# clock.net
KiCad netlist of a schematic drawn in EAGLE
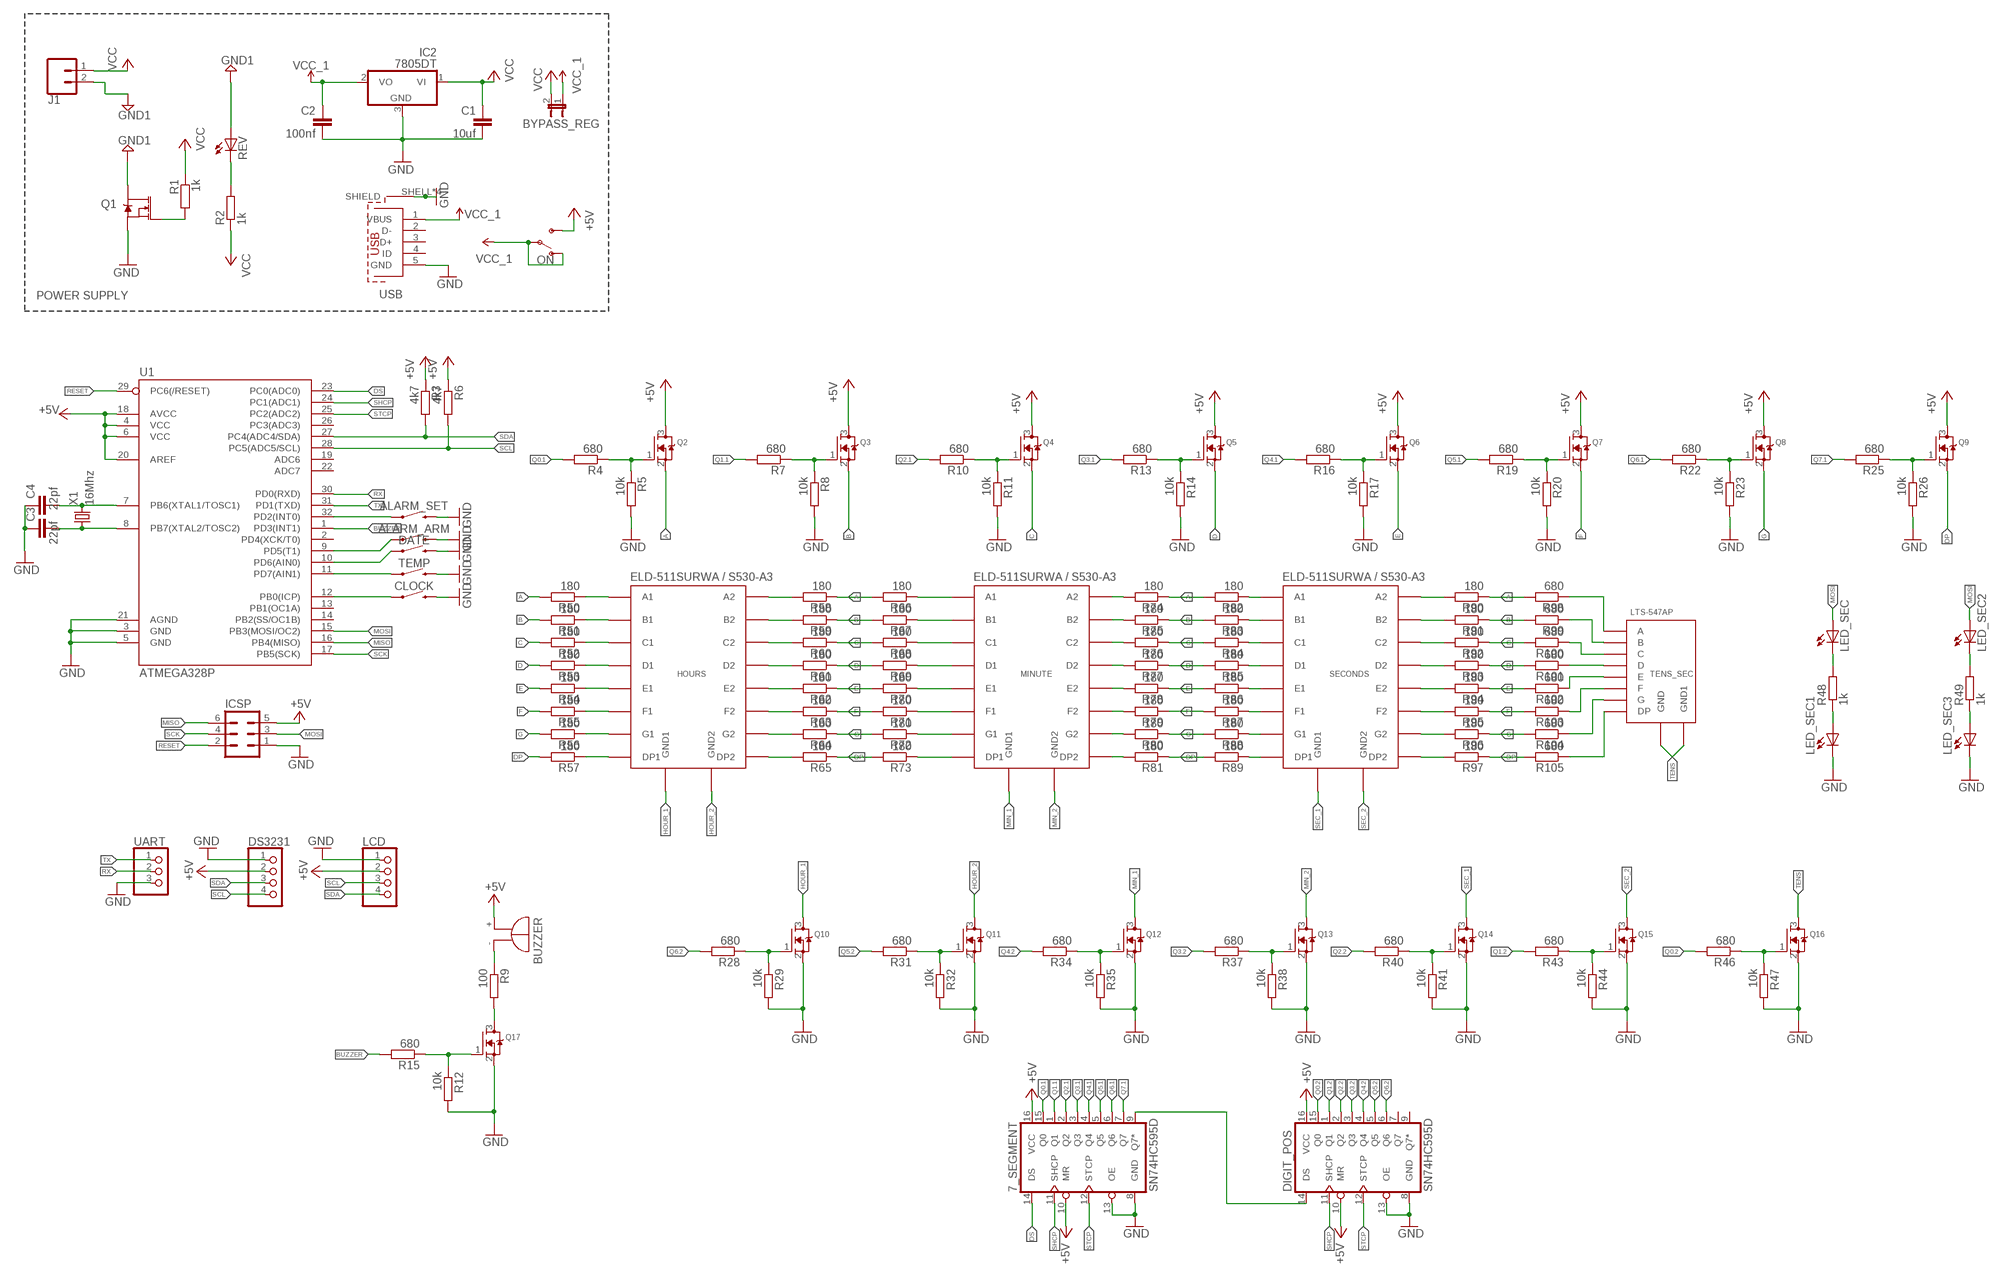
[diagram p0: schematic, sheet 1]

(export (version "E")
  (design (tool "Eeschema 10.0.6"))
  (components
    (comp (ref "7_SEGMENT")
      (value "SN74HC595D")
      (footprint "eagle-import:SO16")
      (libsource (lib "eagle-import") (part "74595DHC"))
    )
    (comp (ref "ALARM_ARM")
      (value "MOMENTARY-SWITCH-SPST-SMD-5.2MM")
      (footprint "eagle-import:TACTILE_SWITCH_SMD_5.2MM")
      (libsource (lib "eagle-import") (part "MOMENTARY-SWITCH-SPST-SMD-5.2MM"))
    )
    (comp (ref "ALARM_SET")
      (value "MOMENTARY-SWITCH-SPST-SMD-5.2MM")
      (footprint "eagle-import:TACTILE_SWITCH_SMD_5.2MM")
      (libsource (lib "eagle-import") (part "MOMENTARY-SWITCH-SPST-SMD-5.2MM"))
    )
    (comp (ref "BUZZER")
      (value "EB2209A")
      (footprint "eagle-import:EB2209A")
      (libsource (lib "eagle-import") (part "EB2209A"))
    )
    (comp (ref "BYPASS_REG")
      (value "JUMPER-2PTH")
      (footprint "eagle-import:1X02")
      (libsource (lib "eagle-import") (part "JUMPER-2PTH"))
    )
    (comp (ref "C1")
      (value "10uf")
      (footprint "eagle-import:C1206")
      (libsource (lib "eagle-import") (part "C-EUC1206"))
    )
    (comp (ref "C2")
      (value "100nf")
      (footprint "eagle-import:C1206")
      (libsource (lib "eagle-import") (part "C-EUC1206"))
    )
    (comp (ref "C3")
      (value "22pf")
      (footprint "eagle-import:C1206")
      (libsource (lib "eagle-import") (part "C-EUC1206"))
    )
    (comp (ref "C4")
      (value "22pf")
      (footprint "eagle-import:C1206")
      (libsource (lib "eagle-import") (part "C-EUC1206"))
    )
    (comp (ref "CLOCK")
      (value "MOMENTARY-SWITCH-SPST-SMD-5.2MM")
      (footprint "eagle-import:TACTILE_SWITCH_SMD_5.2MM")
      (libsource (lib "eagle-import") (part "MOMENTARY-SWITCH-SPST-SMD-5.2MM"))
    )
    (comp (ref "DATE")
      (value "MOMENTARY-SWITCH-SPST-SMD-5.2MM")
      (footprint "eagle-import:TACTILE_SWITCH_SMD_5.2MM")
      (libsource (lib "eagle-import") (part "MOMENTARY-SWITCH-SPST-SMD-5.2MM"))
    )
    (comp (ref "DIGIT_POS")
      (value "SN74HC595D")
      (footprint "eagle-import:SO16")
      (libsource (lib "eagle-import") (part "74595DHC"))
    )
    (comp (ref "DS3231")
      (value "PINHD-1X4")
      (footprint "eagle-import:1X04")
      (libsource (lib "eagle-import") (part "PINHD-1X4"))
    )
    (comp (ref "HOURS")
      (value "ELD-511SURWA/S530-A3")
      (footprint "eagle-import:2_DIGITS_7_SEGMENT")
      (libsource (lib "eagle-import") (part "ELD-511SURWA/S530-A3"))
    )
    (comp (ref "IC2")
      (value "7805DT")
      (footprint "eagle-import:TO252")
      (libsource (lib "eagle-import") (part "78DT05"))
    )
    (comp (ref "ICSP")
      (value "MA03-2")
      (footprint "eagle-import:MA03-2")
      (libsource (lib "eagle-import") (part "MA03-2"))
    )
    (comp (ref "J1")
      (value "CONN_025MM")
      (footprint "eagle-import:SCREWTERMINAL-5MM-2")
      (libsource (lib "eagle-import") (part "CONN_025MM"))
    )
    (comp (ref "LCD")
      (value "PINHD-1X4")
      (footprint "eagle-import:1X04")
      (libsource (lib "eagle-import") (part "PINHD-1X4"))
    )
    (comp (ref "LED_SEC")
      (value "LEDSML0805")
      (footprint "eagle-import:SML0805")
      (libsource (lib "eagle-import") (part "LEDSML0805"))
    )
    (comp (ref "LED_SEC1")
      (value "LEDSML0805")
      (footprint "eagle-import:SML0805")
      (libsource (lib "eagle-import") (part "LEDSML0805"))
    )
    (comp (ref "LED_SEC2")
      (value "LEDSML0805")
      (footprint "eagle-import:SML0805")
      (libsource (lib "eagle-import") (part "LEDSML0805"))
    )
    (comp (ref "LED_SEC3")
      (value "LEDSML0805")
      (footprint "eagle-import:SML0805")
      (libsource (lib "eagle-import") (part "LEDSML0805"))
    )
    (comp (ref "MINUTE")
      (value "ELD-511SURWA/S530-A3")
      (footprint "eagle-import:2_DIGITS_7_SEGMENT")
      (libsource (lib "eagle-import") (part "ELD-511SURWA/S530-A3"))
    )
    (comp (ref "ON")
      (value "SWITCH-SPDT-PTH-11.6X4.0MM")
      (footprint "eagle-import:SWITCH_SPDT_PTH_11.6X4.0MM")
      (libsource (lib "eagle-import") (part "SWITCH-SPDT-PTH-11.6X4.0MM"))
    )
    (comp (ref "Q1")
      (value "MOSFET-NCH-FDD8780")
      (footprint "eagle-import:DPAK")
      (libsource (lib "eagle-import") (part "MOSFET-NCH-FDD8780"))
    )
    (comp (ref "Q2")
      (value "MOSFET-NREFLOW")
      (footprint "eagle-import:SOT23")
      (libsource (lib "eagle-import") (part "MOSFET-NREFLOW"))
    )
    (comp (ref "Q3")
      (value "MOSFET-NREFLOW")
      (footprint "eagle-import:SOT23")
      (libsource (lib "eagle-import") (part "MOSFET-NREFLOW"))
    )
    (comp (ref "Q4")
      (value "MOSFET-NREFLOW")
      (footprint "eagle-import:SOT23")
      (libsource (lib "eagle-import") (part "MOSFET-NREFLOW"))
    )
    (comp (ref "Q5")
      (value "MOSFET-NREFLOW")
      (footprint "eagle-import:SOT23")
      (libsource (lib "eagle-import") (part "MOSFET-NREFLOW"))
    )
    (comp (ref "Q6")
      (value "MOSFET-NREFLOW")
      (footprint "eagle-import:SOT23")
      (libsource (lib "eagle-import") (part "MOSFET-NREFLOW"))
    )
    (comp (ref "Q7")
      (value "MOSFET-NREFLOW")
      (footprint "eagle-import:SOT23")
      (libsource (lib "eagle-import") (part "MOSFET-NREFLOW"))
    )
    (comp (ref "Q8")
      (value "MOSFET-NREFLOW")
      (footprint "eagle-import:SOT23")
      (libsource (lib "eagle-import") (part "MOSFET-NREFLOW"))
    )
    (comp (ref "Q9")
      (value "MOSFET-NREFLOW")
      (footprint "eagle-import:SOT23")
      (libsource (lib "eagle-import") (part "MOSFET-NREFLOW"))
    )
    (comp (ref "Q10")
      (value "MOSFET-NREFLOW")
      (footprint "eagle-import:SOT23")
      (libsource (lib "eagle-import") (part "MOSFET-NREFLOW"))
    )
    (comp (ref "Q11")
      (value "MOSFET-NREFLOW")
      (footprint "eagle-import:SOT23")
      (libsource (lib "eagle-import") (part "MOSFET-NREFLOW"))
    )
    (comp (ref "Q12")
      (value "MOSFET-NREFLOW")
      (footprint "eagle-import:SOT23")
      (libsource (lib "eagle-import") (part "MOSFET-NREFLOW"))
    )
    (comp (ref "Q13")
      (value "MOSFET-NREFLOW")
      (footprint "eagle-import:SOT23")
      (libsource (lib "eagle-import") (part "MOSFET-NREFLOW"))
    )
    (comp (ref "Q14")
      (value "MOSFET-NREFLOW")
      (footprint "eagle-import:SOT23")
      (libsource (lib "eagle-import") (part "MOSFET-NREFLOW"))
    )
    (comp (ref "Q15")
      (value "MOSFET-NREFLOW")
      (footprint "eagle-import:SOT23")
      (libsource (lib "eagle-import") (part "MOSFET-NREFLOW"))
    )
    (comp (ref "Q16")
      (value "MOSFET-NREFLOW")
      (footprint "eagle-import:SOT23")
      (libsource (lib "eagle-import") (part "MOSFET-NREFLOW"))
    )
    (comp (ref "Q17")
      (value "MOSFET-NREFLOW")
      (footprint "eagle-import:SOT23")
      (libsource (lib "eagle-import") (part "MOSFET-NREFLOW"))
    )
    (comp (ref "R1")
      (value "1k")
      (footprint "eagle-import:R0805")
      (libsource (lib "eagle-import") (part "R-EU_R0805"))
    )
    (comp (ref "R2")
      (value "1k")
      (footprint "eagle-import:M0805")
      (libsource (lib "eagle-import") (part "R-EU_M0805"))
    )
    (comp (ref "R3")
      (value "4k7")
      (footprint "eagle-import:M0805")
      (libsource (lib "eagle-import") (part "R-EU_M0805"))
    )
    (comp (ref "R4")
      (value "680")
      (footprint "eagle-import:M0805")
      (libsource (lib "eagle-import") (part "R-EU_M0805"))
    )
    (comp (ref "R5")
      (value "10k")
      (footprint "eagle-import:M0805")
      (libsource (lib "eagle-import") (part "R-EU_M0805"))
    )
    (comp (ref "R6")
      (value "4k7")
      (footprint "eagle-import:M0805")
      (libsource (lib "eagle-import") (part "R-EU_M0805"))
    )
    (comp (ref "R7")
      (value "680")
      (footprint "eagle-import:M0805")
      (libsource (lib "eagle-import") (part "R-EU_M0805"))
    )
    (comp (ref "R8")
      (value "10k")
      (footprint "eagle-import:M0805")
      (libsource (lib "eagle-import") (part "R-EU_M0805"))
    )
    (comp (ref "R9")
      (value "100")
      (footprint "eagle-import:M0805")
      (libsource (lib "eagle-import") (part "R-EU_M0805"))
    )
    (comp (ref "R10")
      (value "680")
      (footprint "eagle-import:M0805")
      (libsource (lib "eagle-import") (part "R-EU_M0805"))
    )
    (comp (ref "R11")
      (value "10k")
      (footprint "eagle-import:M0805")
      (libsource (lib "eagle-import") (part "R-EU_M0805"))
    )
    (comp (ref "R12")
      (value "10k")
      (footprint "eagle-import:M0805")
      (libsource (lib "eagle-import") (part "R-EU_M0805"))
    )
    (comp (ref "R13")
      (value "680")
      (footprint "eagle-import:M0805")
      (libsource (lib "eagle-import") (part "R-EU_M0805"))
    )
    (comp (ref "R14")
      (value "10k")
      (footprint "eagle-import:M0805")
      (libsource (lib "eagle-import") (part "R-EU_M0805"))
    )
    (comp (ref "R15")
      (value "680")
      (footprint "eagle-import:M0805")
      (libsource (lib "eagle-import") (part "R-EU_M0805"))
    )
    (comp (ref "R16")
      (value "680")
      (footprint "eagle-import:M0805")
      (libsource (lib "eagle-import") (part "R-EU_M0805"))
    )
    (comp (ref "R17")
      (value "10k")
      (footprint "eagle-import:M0805")
      (libsource (lib "eagle-import") (part "R-EU_M0805"))
    )
    (comp (ref "R19")
      (value "680")
      (footprint "eagle-import:M0805")
      (libsource (lib "eagle-import") (part "R-EU_M0805"))
    )
    (comp (ref "R20")
      (value "10k")
      (footprint "eagle-import:M0805")
      (libsource (lib "eagle-import") (part "R-EU_M0805"))
    )
    (comp (ref "R22")
      (value "680")
      (footprint "eagle-import:M0805")
      (libsource (lib "eagle-import") (part "R-EU_M0805"))
    )
    (comp (ref "R23")
      (value "10k")
      (footprint "eagle-import:M0805")
      (libsource (lib "eagle-import") (part "R-EU_M0805"))
    )
    (comp (ref "R25")
      (value "680")
      (footprint "eagle-import:M0805")
      (libsource (lib "eagle-import") (part "R-EU_M0805"))
    )
    (comp (ref "R26")
      (value "10k")
      (footprint "eagle-import:M0805")
      (libsource (lib "eagle-import") (part "R-EU_M0805"))
    )
    (comp (ref "R28")
      (value "680")
      (footprint "eagle-import:M0805")
      (libsource (lib "eagle-import") (part "R-EU_M0805"))
    )
    (comp (ref "R29")
      (value "10k")
      (footprint "eagle-import:M0805")
      (libsource (lib "eagle-import") (part "R-EU_M0805"))
    )
    (comp (ref "R31")
      (value "680")
      (footprint "eagle-import:M0805")
      (libsource (lib "eagle-import") (part "R-EU_M0805"))
    )
    (comp (ref "R32")
      (value "10k")
      (footprint "eagle-import:M0805")
      (libsource (lib "eagle-import") (part "R-EU_M0805"))
    )
    (comp (ref "R34")
      (value "680")
      (footprint "eagle-import:M0805")
      (libsource (lib "eagle-import") (part "R-EU_M0805"))
    )
    (comp (ref "R35")
      (value "10k")
      (footprint "eagle-import:M0805")
      (libsource (lib "eagle-import") (part "R-EU_M0805"))
    )
    (comp (ref "R37")
      (value "680")
      (footprint "eagle-import:M0805")
      (libsource (lib "eagle-import") (part "R-EU_M0805"))
    )
    (comp (ref "R38")
      (value "10k")
      (footprint "eagle-import:M0805")
      (libsource (lib "eagle-import") (part "R-EU_M0805"))
    )
    (comp (ref "R40")
      (value "680")
      (footprint "eagle-import:M0805")
      (libsource (lib "eagle-import") (part "R-EU_M0805"))
    )
    (comp (ref "R41")
      (value "10k")
      (footprint "eagle-import:M0805")
      (libsource (lib "eagle-import") (part "R-EU_M0805"))
    )
    (comp (ref "R43")
      (value "680")
      (footprint "eagle-import:M0805")
      (libsource (lib "eagle-import") (part "R-EU_M0805"))
    )
    (comp (ref "R44")
      (value "10k")
      (footprint "eagle-import:M0805")
      (libsource (lib "eagle-import") (part "R-EU_M0805"))
    )
    (comp (ref "R46")
      (value "680")
      (footprint "eagle-import:M0805")
      (libsource (lib "eagle-import") (part "R-EU_M0805"))
    )
    (comp (ref "R47")
      (value "10k")
      (footprint "eagle-import:M0805")
      (libsource (lib "eagle-import") (part "R-EU_M0805"))
    )
    (comp (ref "R48")
      (value "1k")
      (footprint "eagle-import:M0805")
      (libsource (lib "eagle-import") (part "R-EU_M0805"))
    )
    (comp (ref "R49")
      (value "1k")
      (footprint "eagle-import:M0805")
      (libsource (lib "eagle-import") (part "R-EU_M0805"))
    )
    (comp (ref "R50")
      (value "180")
      (footprint "eagle-import:M0805")
      (libsource (lib "eagle-import") (part "R-EU_M0805"))
    )
    (comp (ref "R51")
      (value "180")
      (footprint "eagle-import:M0805")
      (libsource (lib "eagle-import") (part "R-EU_M0805"))
    )
    (comp (ref "R52")
      (value "180")
      (footprint "eagle-import:M0805")
      (libsource (lib "eagle-import") (part "R-EU_M0805"))
    )
    (comp (ref "R53")
      (value "180")
      (footprint "eagle-import:M0805")
      (libsource (lib "eagle-import") (part "R-EU_M0805"))
    )
    (comp (ref "R54")
      (value "180")
      (footprint "eagle-import:M0805")
      (libsource (lib "eagle-import") (part "R-EU_M0805"))
    )
    (comp (ref "R55")
      (value "180")
      (footprint "eagle-import:M0805")
      (libsource (lib "eagle-import") (part "R-EU_M0805"))
    )
    (comp (ref "R56")
      (value "180")
      (footprint "eagle-import:M0805")
      (libsource (lib "eagle-import") (part "R-EU_M0805"))
    )
    (comp (ref "R57")
      (value "180")
      (footprint "eagle-import:M0805")
      (libsource (lib "eagle-import") (part "R-EU_M0805"))
    )
    (comp (ref "R58")
      (value "180")
      (footprint "eagle-import:M0805")
      (libsource (lib "eagle-import") (part "R-EU_M0805"))
    )
    (comp (ref "R59")
      (value "180")
      (footprint "eagle-import:M0805")
      (libsource (lib "eagle-import") (part "R-EU_M0805"))
    )
    (comp (ref "R60")
      (value "180")
      (footprint "eagle-import:M0805")
      (libsource (lib "eagle-import") (part "R-EU_M0805"))
    )
    (comp (ref "R61")
      (value "180")
      (footprint "eagle-import:M0805")
      (libsource (lib "eagle-import") (part "R-EU_M0805"))
    )
    (comp (ref "R62")
      (value "180")
      (footprint "eagle-import:M0805")
      (libsource (lib "eagle-import") (part "R-EU_M0805"))
    )
    (comp (ref "R63")
      (value "180")
      (footprint "eagle-import:M0805")
      (libsource (lib "eagle-import") (part "R-EU_M0805"))
    )
    (comp (ref "R64")
      (value "180")
      (footprint "eagle-import:M0805")
      (libsource (lib "eagle-import") (part "R-EU_M0805"))
    )
    (comp (ref "R65")
      (value "180")
      (footprint "eagle-import:M0805")
      (libsource (lib "eagle-import") (part "R-EU_M0805"))
    )
    (comp (ref "R66")
      (value "180")
      (footprint "eagle-import:M0805")
      (libsource (lib "eagle-import") (part "R-EU_M0805"))
    )
    (comp (ref "R67")
      (value "180")
      (footprint "eagle-import:M0805")
      (libsource (lib "eagle-import") (part "R-EU_M0805"))
    )
    (comp (ref "R68")
      (value "180")
      (footprint "eagle-import:M0805")
      (libsource (lib "eagle-import") (part "R-EU_M0805"))
    )
    (comp (ref "R69")
      (value "180")
      (footprint "eagle-import:M0805")
      (libsource (lib "eagle-import") (part "R-EU_M0805"))
    )
    (comp (ref "R70")
      (value "180")
      (footprint "eagle-import:M0805")
      (libsource (lib "eagle-import") (part "R-EU_M0805"))
    )
    (comp (ref "R71")
      (value "180")
      (footprint "eagle-import:M0805")
      (libsource (lib "eagle-import") (part "R-EU_M0805"))
    )
    (comp (ref "R72")
      (value "180")
      (footprint "eagle-import:M0805")
      (libsource (lib "eagle-import") (part "R-EU_M0805"))
    )
    (comp (ref "R73")
      (value "180")
      (footprint "eagle-import:M0805")
      (libsource (lib "eagle-import") (part "R-EU_M0805"))
    )
    (comp (ref "R74")
      (value "180")
      (footprint "eagle-import:M0805")
      (libsource (lib "eagle-import") (part "R-EU_M0805"))
    )
    (comp (ref "R75")
      (value "180")
      (footprint "eagle-import:M0805")
      (libsource (lib "eagle-import") (part "R-EU_M0805"))
    )
    (comp (ref "R76")
      (value "180")
      (footprint "eagle-import:M0805")
      (libsource (lib "eagle-import") (part "R-EU_M0805"))
    )
    (comp (ref "R77")
      (value "180")
      (footprint "eagle-import:M0805")
      (libsource (lib "eagle-import") (part "R-EU_M0805"))
    )
    (comp (ref "R78")
      (value "180")
      (footprint "eagle-import:M0805")
      (libsource (lib "eagle-import") (part "R-EU_M0805"))
    )
    (comp (ref "R79")
      (value "180")
      (footprint "eagle-import:M0805")
      (libsource (lib "eagle-import") (part "R-EU_M0805"))
    )
    (comp (ref "R80")
      (value "180")
      (footprint "eagle-import:M0805")
      (libsource (lib "eagle-import") (part "R-EU_M0805"))
    )
    (comp (ref "R81")
      (value "180")
      (footprint "eagle-import:M0805")
      (libsource (lib "eagle-import") (part "R-EU_M0805"))
    )
    (comp (ref "R82")
      (value "180")
      (footprint "eagle-import:M0805")
      (libsource (lib "eagle-import") (part "R-EU_M0805"))
    )
    (comp (ref "R83")
      (value "180")
      (footprint "eagle-import:M0805")
      (libsource (lib "eagle-import") (part "R-EU_M0805"))
    )
    (comp (ref "R84")
      (value "180")
      (footprint "eagle-import:M0805")
      (libsource (lib "eagle-import") (part "R-EU_M0805"))
    )
    (comp (ref "R85")
      (value "180")
      (footprint "eagle-import:M0805")
      (libsource (lib "eagle-import") (part "R-EU_M0805"))
    )
    (comp (ref "R86")
      (value "180")
      (footprint "eagle-import:M0805")
      (libsource (lib "eagle-import") (part "R-EU_M0805"))
    )
    (comp (ref "R87")
      (value "180")
      (footprint "eagle-import:M0805")
      (libsource (lib "eagle-import") (part "R-EU_M0805"))
    )
    (comp (ref "R88")
      (value "180")
      (footprint "eagle-import:M0805")
      (libsource (lib "eagle-import") (part "R-EU_M0805"))
    )
    (comp (ref "R89")
      (value "180")
      (footprint "eagle-import:M0805")
      (libsource (lib "eagle-import") (part "R-EU_M0805"))
    )
    (comp (ref "R90")
      (value "180")
      (footprint "eagle-import:M0805")
      (libsource (lib "eagle-import") (part "R-EU_M0805"))
    )
    (comp (ref "R91")
      (value "180")
      (footprint "eagle-import:M0805")
      (libsource (lib "eagle-import") (part "R-EU_M0805"))
    )
    (comp (ref "R92")
      (value "180")
      (footprint "eagle-import:M0805")
      (libsource (lib "eagle-import") (part "R-EU_M0805"))
    )
    (comp (ref "R93")
      (value "180")
      (footprint "eagle-import:M0805")
      (libsource (lib "eagle-import") (part "R-EU_M0805"))
    )
    (comp (ref "R94")
      (value "180")
      (footprint "eagle-import:M0805")
      (libsource (lib "eagle-import") (part "R-EU_M0805"))
    )
    (comp (ref "R95")
      (value "180")
      (footprint "eagle-import:M0805")
      (libsource (lib "eagle-import") (part "R-EU_M0805"))
    )
    (comp (ref "R96")
      (value "180")
      (footprint "eagle-import:M0805")
      (libsource (lib "eagle-import") (part "R-EU_M0805"))
    )
    (comp (ref "R97")
      (value "180")
      (footprint "eagle-import:M0805")
      (libsource (lib "eagle-import") (part "R-EU_M0805"))
    )
    (comp (ref "R98")
      (value "680")
      (footprint "eagle-import:M0805")
      (libsource (lib "eagle-import") (part "R-EU_M0805"))
    )
    (comp (ref "R99")
      (value "680")
      (footprint "eagle-import:M0805")
      (libsource (lib "eagle-import") (part "R-EU_M0805"))
    )
    (comp (ref "R100")
      (value "680")
      (footprint "eagle-import:M0805")
      (libsource (lib "eagle-import") (part "R-EU_M0805"))
    )
    (comp (ref "R101")
      (value "680")
      (footprint "eagle-import:M0805")
      (libsource (lib "eagle-import") (part "R-EU_M0805"))
    )
    (comp (ref "R102")
      (value "680")
      (footprint "eagle-import:M0805")
      (libsource (lib "eagle-import") (part "R-EU_M0805"))
    )
    (comp (ref "R103")
      (value "680")
      (footprint "eagle-import:M0805")
      (libsource (lib "eagle-import") (part "R-EU_M0805"))
    )
    (comp (ref "R104")
      (value "680")
      (footprint "eagle-import:M0805")
      (libsource (lib "eagle-import") (part "R-EU_M0805"))
    )
    (comp (ref "R105")
      (value "680")
      (footprint "eagle-import:M0805")
      (libsource (lib "eagle-import") (part "R-EU_M0805"))
    )
    (comp (ref "REV")
      (value "LEDSML0805")
      (footprint "eagle-import:SML0805")
      (libsource (lib "eagle-import") (part "LEDSML0805"))
    )
    (comp (ref "SECONDS")
      (value "ELD-511SURWA/S530-A3")
      (footprint "eagle-import:2_DIGITS_7_SEGMENT")
      (libsource (lib "eagle-import") (part "ELD-511SURWA/S530-A3"))
    )
    (comp (ref "TEMP")
      (value "MOMENTARY-SWITCH-SPST-SMD-5.2MM")
      (footprint "eagle-import:TACTILE_SWITCH_SMD_5.2MM")
      (libsource (lib "eagle-import") (part "MOMENTARY-SWITCH-SPST-SMD-5.2MM"))
    )
    (comp (ref "TENS_SEC")
      (value "LTS-547AP")
      (footprint "eagle-import:LTS-547AP")
      (libsource (lib "eagle-import") (part "LTS-547AP"))
    )
    (comp (ref "U1")
      (value "ATMEGA328P")
      (footprint "eagle-import:TQFP32-08")
      (libsource (lib "eagle-import") (part "ATMEGA328P_TQFP"))
    )
    (comp (ref "UART")
      (value "PINHD-1X3")
      (footprint "eagle-import:1X03")
      (libsource (lib "eagle-import") (part "PINHD-1X3"))
    )
    (comp (ref "USB")
      (value "629105136821")
      (footprint "eagle-import:629105136821")
      (libsource (lib "eagle-import") (part "629105136821"))
    )
    (comp (ref "X1")
      (value "16Mhz")
      (footprint "eagle-import:SM49")
      (libsource (lib "eagle-import") (part "CRYSTALSM49"))
    )
  )
  (nets
    (net (code "1") (name "+5V") (class "Default")
      (node (ref "7_SEGMENT") (pin "10") (pinfunction "MR_10") (pintype "input"))
      (node (ref "7_SEGMENT") (pin "16") (pinfunction "VCC_16") (pintype "power_in"))
      (node (ref "BUZZER") (pin "+") (pinfunction "+_+") (pintype "passive"))
      (node (ref "DIGIT_POS") (pin "10") (pinfunction "MR_10") (pintype "input"))
      (node (ref "DIGIT_POS") (pin "16") (pinfunction "VCC_16") (pintype "power_in"))
      (node (ref "DS3231") (pin "2") (pinfunction "2_2") (pintype "passive"))
      (node (ref "ICSP") (pin "5") (pinfunction "5_5") (pintype "passive"))
      (node (ref "LCD") (pin "2") (pinfunction "2_2") (pintype "passive"))
      (node (ref "ON") (pin "3") (pinfunction "S_3") (pintype "passive"))
      (node (ref "Q2") (pin "3") (pinfunction "D_3") (pintype "bidirectional"))
      (node (ref "Q3") (pin "3") (pinfunction "D_3") (pintype "bidirectional"))
      (node (ref "Q4") (pin "3") (pinfunction "D_3") (pintype "bidirectional"))
      (node (ref "Q5") (pin "3") (pinfunction "D_3") (pintype "bidirectional"))
      (node (ref "Q6") (pin "3") (pinfunction "D_3") (pintype "bidirectional"))
      (node (ref "Q7") (pin "3") (pinfunction "D_3") (pintype "bidirectional"))
      (node (ref "Q8") (pin "3") (pinfunction "D_3") (pintype "bidirectional"))
      (node (ref "Q9") (pin "3") (pinfunction "D_3") (pintype "bidirectional"))
      (node (ref "R3") (pin "1") (pinfunction "1_1") (pintype "passive"))
      (node (ref "R6") (pin "1") (pinfunction "1_1") (pintype "passive"))
      (node (ref "U1") (pin "18") (pinfunction "AVCC_18") (pintype "bidirectional"))
      (node (ref "U1") (pin "20") (pinfunction "AREF_20") (pintype "bidirectional"))
      (node (ref "U1") (pin "4") (pinfunction "VCC_4") (pintype "bidirectional"))
      (node (ref "U1") (pin "6") (pinfunction "VCC_6") (pintype "bidirectional"))
    )
    (net (code "2") (name "A") (class "Default")
      (node (ref "Q2") (pin "2") (pinfunction "S_2") (pintype "bidirectional"))
      (node (ref "R50") (pin "2") (pinfunction "2_2") (pintype "passive"))
      (node (ref "R58") (pin "1") (pinfunction "1_1") (pintype "passive"))
      (node (ref "R66") (pin "2") (pinfunction "2_2") (pintype "passive"))
      (node (ref "R74") (pin "1") (pinfunction "1_1") (pintype "passive"))
      (node (ref "R82") (pin "2") (pinfunction "2_2") (pintype "passive"))
      (node (ref "R90") (pin "1") (pinfunction "1_1") (pintype "passive"))
      (node (ref "R98") (pin "2") (pinfunction "2_2") (pintype "passive"))
    )
    (net (code "3") (name "B") (class "Default")
      (node (ref "Q3") (pin "2") (pinfunction "S_2") (pintype "bidirectional"))
      (node (ref "R51") (pin "2") (pinfunction "2_2") (pintype "passive"))
      (node (ref "R59") (pin "1") (pinfunction "1_1") (pintype "passive"))
      (node (ref "R67") (pin "2") (pinfunction "2_2") (pintype "passive"))
      (node (ref "R75") (pin "1") (pinfunction "1_1") (pintype "passive"))
      (node (ref "R83") (pin "2") (pinfunction "2_2") (pintype "passive"))
      (node (ref "R91") (pin "1") (pinfunction "1_1") (pintype "passive"))
      (node (ref "R99") (pin "2") (pinfunction "2_2") (pintype "passive"))
    )
    (net (code "4") (name "BUZZER") (class "Default")
      (node (ref "R15") (pin "2") (pinfunction "2_2") (pintype "passive"))
      (node (ref "U1") (pin "1") (pinfunction "PD3(INT1)_1") (pintype "bidirectional"))
    )
    (net (code "5") (name "C") (class "Default")
      (node (ref "Q4") (pin "2") (pinfunction "S_2") (pintype "bidirectional"))
      (node (ref "R100") (pin "2") (pinfunction "2_2") (pintype "passive"))
      (node (ref "R52") (pin "2") (pinfunction "2_2") (pintype "passive"))
      (node (ref "R60") (pin "1") (pinfunction "1_1") (pintype "passive"))
      (node (ref "R68") (pin "2") (pinfunction "2_2") (pintype "passive"))
      (node (ref "R76") (pin "1") (pinfunction "1_1") (pintype "passive"))
      (node (ref "R84") (pin "2") (pinfunction "2_2") (pintype "passive"))
      (node (ref "R92") (pin "1") (pinfunction "1_1") (pintype "passive"))
    )
    (net (code "6") (name "D") (class "Default")
      (node (ref "Q5") (pin "2") (pinfunction "S_2") (pintype "bidirectional"))
      (node (ref "R101") (pin "2") (pinfunction "2_2") (pintype "passive"))
      (node (ref "R53") (pin "2") (pinfunction "2_2") (pintype "passive"))
      (node (ref "R61") (pin "1") (pinfunction "1_1") (pintype "passive"))
      (node (ref "R69") (pin "2") (pinfunction "2_2") (pintype "passive"))
      (node (ref "R77") (pin "1") (pinfunction "1_1") (pintype "passive"))
      (node (ref "R85") (pin "2") (pinfunction "2_2") (pintype "passive"))
      (node (ref "R93") (pin "1") (pinfunction "1_1") (pintype "passive"))
    )
    (net (code "7") (name "DP") (class "Default")
      (node (ref "Q9") (pin "2") (pinfunction "S_2") (pintype "bidirectional"))
      (node (ref "R105") (pin "2") (pinfunction "2_2") (pintype "passive"))
      (node (ref "R57") (pin "2") (pinfunction "2_2") (pintype "passive"))
      (node (ref "R65") (pin "1") (pinfunction "1_1") (pintype "passive"))
      (node (ref "R73") (pin "2") (pinfunction "2_2") (pintype "passive"))
      (node (ref "R81") (pin "1") (pinfunction "1_1") (pintype "passive"))
      (node (ref "R89") (pin "2") (pinfunction "2_2") (pintype "passive"))
      (node (ref "R97") (pin "1") (pinfunction "1_1") (pintype "passive"))
    )
    (net (code "8") (name "DS") (class "Default")
      (node (ref "7_SEGMENT") (pin "14") (pinfunction "DS_14") (pintype "input"))
      (node (ref "U1") (pin "23") (pinfunction "PC0(ADC0)_23") (pintype "bidirectional"))
    )
    (net (code "9") (name "E") (class "Default")
      (node (ref "Q6") (pin "2") (pinfunction "S_2") (pintype "bidirectional"))
      (node (ref "R102") (pin "2") (pinfunction "2_2") (pintype "passive"))
      (node (ref "R54") (pin "2") (pinfunction "2_2") (pintype "passive"))
      (node (ref "R62") (pin "1") (pinfunction "1_1") (pintype "passive"))
      (node (ref "R70") (pin "2") (pinfunction "2_2") (pintype "passive"))
      (node (ref "R78") (pin "1") (pinfunction "1_1") (pintype "passive"))
      (node (ref "R86") (pin "2") (pinfunction "2_2") (pintype "passive"))
      (node (ref "R94") (pin "1") (pinfunction "1_1") (pintype "passive"))
    )
    (net (code "10") (name "F") (class "Default")
      (node (ref "Q7") (pin "2") (pinfunction "S_2") (pintype "bidirectional"))
      (node (ref "R103") (pin "2") (pinfunction "2_2") (pintype "passive"))
      (node (ref "R55") (pin "2") (pinfunction "2_2") (pintype "passive"))
      (node (ref "R63") (pin "1") (pinfunction "1_1") (pintype "passive"))
      (node (ref "R71") (pin "2") (pinfunction "2_2") (pintype "passive"))
      (node (ref "R79") (pin "1") (pinfunction "1_1") (pintype "passive"))
      (node (ref "R87") (pin "2") (pinfunction "2_2") (pintype "passive"))
      (node (ref "R95") (pin "1") (pinfunction "1_1") (pintype "passive"))
    )
    (net (code "11") (name "G") (class "Default")
      (node (ref "Q8") (pin "2") (pinfunction "S_2") (pintype "bidirectional"))
      (node (ref "R104") (pin "2") (pinfunction "2_2") (pintype "passive"))
      (node (ref "R56") (pin "2") (pinfunction "2_2") (pintype "passive"))
      (node (ref "R64") (pin "1") (pinfunction "1_1") (pintype "passive"))
      (node (ref "R72") (pin "2") (pinfunction "2_2") (pintype "passive"))
      (node (ref "R80") (pin "1") (pinfunction "1_1") (pintype "passive"))
      (node (ref "R88") (pin "2") (pinfunction "2_2") (pintype "passive"))
      (node (ref "R96") (pin "1") (pinfunction "1_1") (pintype "passive"))
    )
    (net (code "12") (name "GND") (class "Default")
      (node (ref "7_SEGMENT") (pin "13") (pinfunction "OE_13") (pintype "input"))
      (node (ref "7_SEGMENT") (pin "8") (pinfunction "GND_8") (pintype "power_in"))
      (node (ref "ALARM_ARM") (pin "3") (pinfunction "2_3") (pintype "passive"))
      (node (ref "ALARM_SET") (pin "3") (pinfunction "2_3") (pintype "passive"))
      (node (ref "C1") (pin "2") (pinfunction "2_2") (pintype "passive"))
      (node (ref "C2") (pin "2") (pinfunction "2_2") (pintype "passive"))
      (node (ref "C3") (pin "1") (pinfunction "1_1") (pintype "passive"))
      (node (ref "C4") (pin "1") (pinfunction "1_1") (pintype "passive"))
      (node (ref "CLOCK") (pin "3") (pinfunction "2_3") (pintype "passive"))
      (node (ref "DATE") (pin "3") (pinfunction "2_3") (pintype "passive"))
      (node (ref "DIGIT_POS") (pin "13") (pinfunction "OE_13") (pintype "input"))
      (node (ref "DIGIT_POS") (pin "8") (pinfunction "GND_8") (pintype "power_in"))
      (node (ref "DS3231") (pin "1") (pinfunction "1_1") (pintype "passive"))
      (node (ref "IC2") (pin "3") (pinfunction "GND_3") (pintype "passive"))
      (node (ref "ICSP") (pin "1") (pinfunction "1_1") (pintype "passive"))
      (node (ref "LCD") (pin "1") (pinfunction "1_1") (pintype "passive"))
      (node (ref "LED_SEC1") (pin "C") (pinfunction "C_C") (pintype "passive"))
      (node (ref "LED_SEC3") (pin "C") (pinfunction "C_C") (pintype "passive"))
      (node (ref "Q1") (pin "3") (pinfunction "S_3") (pintype "bidirectional"))
      (node (ref "Q10") (pin "2") (pinfunction "S_2") (pintype "bidirectional"))
      (node (ref "Q11") (pin "2") (pinfunction "S_2") (pintype "bidirectional"))
      (node (ref "Q12") (pin "2") (pinfunction "S_2") (pintype "bidirectional"))
      (node (ref "Q13") (pin "2") (pinfunction "S_2") (pintype "bidirectional"))
      (node (ref "Q14") (pin "2") (pinfunction "S_2") (pintype "bidirectional"))
      (node (ref "Q15") (pin "2") (pinfunction "S_2") (pintype "bidirectional"))
      (node (ref "Q16") (pin "2") (pinfunction "S_2") (pintype "bidirectional"))
      (node (ref "Q17") (pin "2") (pinfunction "S_2") (pintype "bidirectional"))
      (node (ref "R11") (pin "2") (pinfunction "2_2") (pintype "passive"))
      (node (ref "R12") (pin "2") (pinfunction "2_2") (pintype "passive"))
      (node (ref "R14") (pin "2") (pinfunction "2_2") (pintype "passive"))
      (node (ref "R17") (pin "2") (pinfunction "2_2") (pintype "passive"))
      (node (ref "R20") (pin "2") (pinfunction "2_2") (pintype "passive"))
      (node (ref "R23") (pin "2") (pinfunction "2_2") (pintype "passive"))
      (node (ref "R26") (pin "2") (pinfunction "2_2") (pintype "passive"))
      (node (ref "R29") (pin "2") (pinfunction "2_2") (pintype "passive"))
      (node (ref "R32") (pin "2") (pinfunction "2_2") (pintype "passive"))
      (node (ref "R35") (pin "2") (pinfunction "2_2") (pintype "passive"))
      (node (ref "R38") (pin "2") (pinfunction "2_2") (pintype "passive"))
      (node (ref "R41") (pin "2") (pinfunction "2_2") (pintype "passive"))
      (node (ref "R44") (pin "2") (pinfunction "2_2") (pintype "passive"))
      (node (ref "R47") (pin "2") (pinfunction "2_2") (pintype "passive"))
      (node (ref "R5") (pin "2") (pinfunction "2_2") (pintype "passive"))
      (node (ref "R8") (pin "2") (pinfunction "2_2") (pintype "passive"))
      (node (ref "TEMP") (pin "3") (pinfunction "2_3") (pintype "passive"))
      (node (ref "U1") (pin "21") (pinfunction "AGND_21") (pintype "bidirectional"))
      (node (ref "U1") (pin "3") (pinfunction "GND_3") (pintype "bidirectional"))
      (node (ref "U1") (pin "5") (pinfunction "GND_5") (pintype "bidirectional"))
      (node (ref "UART") (pin "3") (pinfunction "3_3") (pintype "passive"))
      (node (ref "USB") (pin "5") (pinfunction "GND_5") (pintype "passive"))
      (node (ref "USB") (pin "SHELL") (pinfunction "SHIELD_SHELL") (pintype "passive"))
      (node (ref "USB") (pin "SHELL1") (pinfunction "SHIELD_SHELL1") (pintype "passive"))
      (node (ref "USB") (pin "SHELL2") (pinfunction "SHIELD_SHELL2") (pintype "passive"))
      (node (ref "USB") (pin "SHELL3") (pinfunction "SHIELD_SHELL3") (pintype "passive"))
    )
    (net (code "13") (name "GND1") (class "Default")
      (node (ref "J1") (pin "2") (pinfunction "2_2") (pintype "passive"))
      (node (ref "Q1") (pin "4") (pinfunction "D_4") (pintype "bidirectional"))
      (node (ref "REV") (pin "A") (pinfunction "A_A") (pintype "passive"))
    )
    (net (code "14") (name "HOUR_1") (class "Default")
      (node (ref "HOURS") (pin "GND1") (pinfunction "GND1_GND1") (pintype "bidirectional"))
      (node (ref "Q10") (pin "3") (pinfunction "D_3") (pintype "bidirectional"))
    )
    (net (code "15") (name "HOUR_2") (class "Default")
      (node (ref "HOURS") (pin "GND2") (pinfunction "GND2_GND2") (pintype "bidirectional"))
      (node (ref "Q11") (pin "3") (pinfunction "D_3") (pintype "bidirectional"))
    )
    (net (code "16") (name "MIN_1") (class "Default")
      (node (ref "MINUTE") (pin "GND1") (pinfunction "GND1_GND1") (pintype "bidirectional"))
      (node (ref "Q12") (pin "3") (pinfunction "D_3") (pintype "bidirectional"))
    )
    (net (code "17") (name "MIN_2") (class "Default")
      (node (ref "MINUTE") (pin "GND2") (pinfunction "GND2_GND2") (pintype "bidirectional"))
      (node (ref "Q13") (pin "3") (pinfunction "D_3") (pintype "bidirectional"))
    )
    (net (code "18") (name "MISO") (class "Default")
      (node (ref "ICSP") (pin "6") (pinfunction "6_6") (pintype "passive"))
      (node (ref "U1") (pin "16") (pinfunction "PB4(MISO)_16") (pintype "bidirectional"))
    )
    (net (code "19") (name "MOSI") (class "Default")
      (node (ref "ICSP") (pin "3") (pinfunction "3_3") (pintype "passive"))
      (node (ref "LED_SEC") (pin "A") (pinfunction "A_A") (pintype "passive"))
      (node (ref "LED_SEC2") (pin "A") (pinfunction "A_A") (pintype "passive"))
      (node (ref "U1") (pin "15") (pinfunction "PB3(MOSI/OC2)_15") (pintype "bidirectional"))
    )
    (net (code "20") (name "Net-(7_SEGMENT-Q7*)") (class "Default")
      (node (ref "7_SEGMENT") (pin "9") (pinfunction "Q7*_9") (pintype "tri_state"))
      (node (ref "DIGIT_POS") (pin "14") (pinfunction "DS_14") (pintype "input"))
    )
    (net (code "21") (name "Net-(BUZZER-Pad-)") (class "Default")
      (node (ref "BUZZER") (pin "-") (pinfunction "-_-") (pintype "passive"))
      (node (ref "R9") (pin "1") (pinfunction "1_1") (pintype "passive"))
    )
    (net (code "22") (name "Net-(HOURS-PadA1)") (class "Default")
      (node (ref "HOURS") (pin "A1") (pinfunction "A1_A1") (pintype "bidirectional"))
      (node (ref "R50") (pin "1") (pinfunction "1_1") (pintype "passive"))
    )
    (net (code "23") (name "Net-(HOURS-PadA2)") (class "Default")
      (node (ref "HOURS") (pin "A2") (pinfunction "A2_A2") (pintype "bidirectional"))
      (node (ref "R58") (pin "2") (pinfunction "2_2") (pintype "passive"))
    )
    (net (code "24") (name "Net-(HOURS-PadB1)") (class "Default")
      (node (ref "HOURS") (pin "B1") (pinfunction "B1_B1") (pintype "bidirectional"))
      (node (ref "R51") (pin "1") (pinfunction "1_1") (pintype "passive"))
    )
    (net (code "25") (name "Net-(HOURS-PadB2)") (class "Default")
      (node (ref "HOURS") (pin "B2") (pinfunction "B2_B2") (pintype "bidirectional"))
      (node (ref "R59") (pin "2") (pinfunction "2_2") (pintype "passive"))
    )
    (net (code "26") (name "Net-(HOURS-PadC1)") (class "Default")
      (node (ref "HOURS") (pin "C1") (pinfunction "C1_C1") (pintype "bidirectional"))
      (node (ref "R52") (pin "1") (pinfunction "1_1") (pintype "passive"))
    )
    (net (code "27") (name "Net-(HOURS-PadC2)") (class "Default")
      (node (ref "HOURS") (pin "C2") (pinfunction "C2_C2") (pintype "bidirectional"))
      (node (ref "R60") (pin "2") (pinfunction "2_2") (pintype "passive"))
    )
    (net (code "28") (name "Net-(HOURS-PadD1)") (class "Default")
      (node (ref "HOURS") (pin "D1") (pinfunction "D1_D1") (pintype "bidirectional"))
      (node (ref "R53") (pin "1") (pinfunction "1_1") (pintype "passive"))
    )
    (net (code "29") (name "Net-(HOURS-PadD2)") (class "Default")
      (node (ref "HOURS") (pin "D2") (pinfunction "D2_D2") (pintype "bidirectional"))
      (node (ref "R61") (pin "2") (pinfunction "2_2") (pintype "passive"))
    )
    (net (code "30") (name "Net-(HOURS-PadDP1)") (class "Default")
      (node (ref "HOURS") (pin "DP1") (pinfunction "DP1_DP1") (pintype "bidirectional"))
      (node (ref "R57") (pin "1") (pinfunction "1_1") (pintype "passive"))
    )
    (net (code "31") (name "Net-(HOURS-PadDP2)") (class "Default")
      (node (ref "HOURS") (pin "DP2") (pinfunction "DP2_DP2") (pintype "bidirectional"))
      (node (ref "R65") (pin "2") (pinfunction "2_2") (pintype "passive"))
    )
    (net (code "32") (name "Net-(HOURS-PadE1)") (class "Default")
      (node (ref "HOURS") (pin "E1") (pinfunction "E1_E1") (pintype "bidirectional"))
      (node (ref "R54") (pin "1") (pinfunction "1_1") (pintype "passive"))
    )
    (net (code "33") (name "Net-(HOURS-PadE2)") (class "Default")
      (node (ref "HOURS") (pin "E2") (pinfunction "E2_E2") (pintype "bidirectional"))
      (node (ref "R62") (pin "2") (pinfunction "2_2") (pintype "passive"))
    )
    (net (code "34") (name "Net-(HOURS-PadF1)") (class "Default")
      (node (ref "HOURS") (pin "F1") (pinfunction "F1_F1") (pintype "bidirectional"))
      (node (ref "R55") (pin "1") (pinfunction "1_1") (pintype "passive"))
    )
    (net (code "35") (name "Net-(HOURS-PadF2)") (class "Default")
      (node (ref "HOURS") (pin "F2") (pinfunction "F2_F2") (pintype "bidirectional"))
      (node (ref "R63") (pin "2") (pinfunction "2_2") (pintype "passive"))
    )
    (net (code "36") (name "Net-(HOURS-PadG1)") (class "Default")
      (node (ref "HOURS") (pin "G1") (pinfunction "G1_G1") (pintype "bidirectional"))
      (node (ref "R56") (pin "1") (pinfunction "1_1") (pintype "passive"))
    )
    (net (code "37") (name "Net-(HOURS-PadG2)") (class "Default")
      (node (ref "HOURS") (pin "G2") (pinfunction "G2_G2") (pintype "bidirectional"))
      (node (ref "R64") (pin "2") (pinfunction "2_2") (pintype "passive"))
    )
    (net (code "38") (name "Net-(LED_SEC-PadC)") (class "Default")
      (node (ref "LED_SEC") (pin "C") (pinfunction "C_C") (pintype "passive"))
      (node (ref "R48") (pin "2") (pinfunction "2_2") (pintype "passive"))
    )
    (net (code "39") (name "Net-(LED_SEC1-PadA)") (class "Default")
      (node (ref "LED_SEC1") (pin "A") (pinfunction "A_A") (pintype "passive"))
      (node (ref "R48") (pin "1") (pinfunction "1_1") (pintype "passive"))
    )
    (net (code "40") (name "Net-(LED_SEC2-PadC)") (class "Default")
      (node (ref "LED_SEC2") (pin "C") (pinfunction "C_C") (pintype "passive"))
      (node (ref "R49") (pin "2") (pinfunction "2_2") (pintype "passive"))
    )
    (net (code "41") (name "Net-(LED_SEC3-PadA)") (class "Default")
      (node (ref "LED_SEC3") (pin "A") (pinfunction "A_A") (pintype "passive"))
      (node (ref "R49") (pin "1") (pinfunction "1_1") (pintype "passive"))
    )
    (net (code "42") (name "Net-(MINUTE-PadA1)") (class "Default")
      (node (ref "MINUTE") (pin "A1") (pinfunction "A1_A1") (pintype "bidirectional"))
      (node (ref "R66") (pin "1") (pinfunction "1_1") (pintype "passive"))
    )
    (net (code "43") (name "Net-(MINUTE-PadA2)") (class "Default")
      (node (ref "MINUTE") (pin "A2") (pinfunction "A2_A2") (pintype "bidirectional"))
      (node (ref "R74") (pin "2") (pinfunction "2_2") (pintype "passive"))
    )
    (net (code "44") (name "Net-(MINUTE-PadB1)") (class "Default")
      (node (ref "MINUTE") (pin "B1") (pinfunction "B1_B1") (pintype "bidirectional"))
      (node (ref "R67") (pin "1") (pinfunction "1_1") (pintype "passive"))
    )
    (net (code "45") (name "Net-(MINUTE-PadB2)") (class "Default")
      (node (ref "MINUTE") (pin "B2") (pinfunction "B2_B2") (pintype "bidirectional"))
      (node (ref "R75") (pin "2") (pinfunction "2_2") (pintype "passive"))
    )
    (net (code "46") (name "Net-(MINUTE-PadC1)") (class "Default")
      (node (ref "MINUTE") (pin "C1") (pinfunction "C1_C1") (pintype "bidirectional"))
      (node (ref "R68") (pin "1") (pinfunction "1_1") (pintype "passive"))
    )
    (net (code "47") (name "Net-(MINUTE-PadC2)") (class "Default")
      (node (ref "MINUTE") (pin "C2") (pinfunction "C2_C2") (pintype "bidirectional"))
      (node (ref "R76") (pin "2") (pinfunction "2_2") (pintype "passive"))
    )
    (net (code "48") (name "Net-(MINUTE-PadD1)") (class "Default")
      (node (ref "MINUTE") (pin "D1") (pinfunction "D1_D1") (pintype "bidirectional"))
      (node (ref "R69") (pin "1") (pinfunction "1_1") (pintype "passive"))
    )
    (net (code "49") (name "Net-(MINUTE-PadD2)") (class "Default")
      (node (ref "MINUTE") (pin "D2") (pinfunction "D2_D2") (pintype "bidirectional"))
      (node (ref "R77") (pin "2") (pinfunction "2_2") (pintype "passive"))
    )
    (net (code "50") (name "Net-(MINUTE-PadDP1)") (class "Default")
      (node (ref "MINUTE") (pin "DP1") (pinfunction "DP1_DP1") (pintype "bidirectional"))
      (node (ref "R73") (pin "1") (pinfunction "1_1") (pintype "passive"))
    )
    (net (code "51") (name "Net-(MINUTE-PadDP2)") (class "Default")
      (node (ref "MINUTE") (pin "DP2") (pinfunction "DP2_DP2") (pintype "bidirectional"))
      (node (ref "R81") (pin "2") (pinfunction "2_2") (pintype "passive"))
    )
    (net (code "52") (name "Net-(MINUTE-PadE1)") (class "Default")
      (node (ref "MINUTE") (pin "E1") (pinfunction "E1_E1") (pintype "bidirectional"))
      (node (ref "R70") (pin "1") (pinfunction "1_1") (pintype "passive"))
    )
    (net (code "53") (name "Net-(MINUTE-PadE2)") (class "Default")
      (node (ref "MINUTE") (pin "E2") (pinfunction "E2_E2") (pintype "bidirectional"))
      (node (ref "R78") (pin "2") (pinfunction "2_2") (pintype "passive"))
    )
    (net (code "54") (name "Net-(MINUTE-PadF1)") (class "Default")
      (node (ref "MINUTE") (pin "F1") (pinfunction "F1_F1") (pintype "bidirectional"))
      (node (ref "R71") (pin "1") (pinfunction "1_1") (pintype "passive"))
    )
    (net (code "55") (name "Net-(MINUTE-PadF2)") (class "Default")
      (node (ref "MINUTE") (pin "F2") (pinfunction "F2_F2") (pintype "bidirectional"))
      (node (ref "R79") (pin "2") (pinfunction "2_2") (pintype "passive"))
    )
    (net (code "56") (name "Net-(MINUTE-PadG1)") (class "Default")
      (node (ref "MINUTE") (pin "G1") (pinfunction "G1_G1") (pintype "bidirectional"))
      (node (ref "R72") (pin "1") (pinfunction "1_1") (pintype "passive"))
    )
    (net (code "57") (name "Net-(MINUTE-PadG2)") (class "Default")
      (node (ref "MINUTE") (pin "G2") (pinfunction "G2_G2") (pintype "bidirectional"))
      (node (ref "R80") (pin "2") (pinfunction "2_2") (pintype "passive"))
    )
    (net (code "58") (name "Net-(Q1-G)") (class "Default")
      (node (ref "Q1") (pin "1") (pinfunction "G_1") (pintype "bidirectional"))
      (node (ref "R1") (pin "2") (pinfunction "2_2") (pintype "passive"))
    )
    (net (code "59") (name "Net-(Q2-G)") (class "Default")
      (node (ref "Q2") (pin "1") (pinfunction "G_1") (pintype "bidirectional"))
      (node (ref "R4") (pin "1") (pinfunction "1_1") (pintype "passive"))
      (node (ref "R5") (pin "1") (pinfunction "1_1") (pintype "passive"))
    )
    (net (code "60") (name "Net-(Q3-G)") (class "Default")
      (node (ref "Q3") (pin "1") (pinfunction "G_1") (pintype "bidirectional"))
      (node (ref "R7") (pin "1") (pinfunction "1_1") (pintype "passive"))
      (node (ref "R8") (pin "1") (pinfunction "1_1") (pintype "passive"))
    )
    (net (code "61") (name "Net-(Q4-G)") (class "Default")
      (node (ref "Q4") (pin "1") (pinfunction "G_1") (pintype "bidirectional"))
      (node (ref "R10") (pin "1") (pinfunction "1_1") (pintype "passive"))
      (node (ref "R11") (pin "1") (pinfunction "1_1") (pintype "passive"))
    )
    (net (code "62") (name "Net-(Q5-G)") (class "Default")
      (node (ref "Q5") (pin "1") (pinfunction "G_1") (pintype "bidirectional"))
      (node (ref "R13") (pin "1") (pinfunction "1_1") (pintype "passive"))
      (node (ref "R14") (pin "1") (pinfunction "1_1") (pintype "passive"))
    )
    (net (code "63") (name "Net-(Q6-G)") (class "Default")
      (node (ref "Q6") (pin "1") (pinfunction "G_1") (pintype "bidirectional"))
      (node (ref "R16") (pin "1") (pinfunction "1_1") (pintype "passive"))
      (node (ref "R17") (pin "1") (pinfunction "1_1") (pintype "passive"))
    )
    (net (code "64") (name "Net-(Q7-G)") (class "Default")
      (node (ref "Q7") (pin "1") (pinfunction "G_1") (pintype "bidirectional"))
      (node (ref "R19") (pin "1") (pinfunction "1_1") (pintype "passive"))
      (node (ref "R20") (pin "1") (pinfunction "1_1") (pintype "passive"))
    )
    (net (code "65") (name "Net-(Q8-G)") (class "Default")
      (node (ref "Q8") (pin "1") (pinfunction "G_1") (pintype "bidirectional"))
      (node (ref "R22") (pin "1") (pinfunction "1_1") (pintype "passive"))
      (node (ref "R23") (pin "1") (pinfunction "1_1") (pintype "passive"))
    )
    (net (code "66") (name "Net-(Q9-G)") (class "Default")
      (node (ref "Q9") (pin "1") (pinfunction "G_1") (pintype "bidirectional"))
      (node (ref "R25") (pin "1") (pinfunction "1_1") (pintype "passive"))
      (node (ref "R26") (pin "1") (pinfunction "1_1") (pintype "passive"))
    )
    (net (code "67") (name "Net-(Q10-G)") (class "Default")
      (node (ref "Q10") (pin "1") (pinfunction "G_1") (pintype "bidirectional"))
      (node (ref "R28") (pin "1") (pinfunction "1_1") (pintype "passive"))
      (node (ref "R29") (pin "1") (pinfunction "1_1") (pintype "passive"))
    )
    (net (code "68") (name "Net-(Q11-G)") (class "Default")
      (node (ref "Q11") (pin "1") (pinfunction "G_1") (pintype "bidirectional"))
      (node (ref "R31") (pin "1") (pinfunction "1_1") (pintype "passive"))
      (node (ref "R32") (pin "1") (pinfunction "1_1") (pintype "passive"))
    )
    (net (code "69") (name "Net-(Q12-G)") (class "Default")
      (node (ref "Q12") (pin "1") (pinfunction "G_1") (pintype "bidirectional"))
      (node (ref "R34") (pin "1") (pinfunction "1_1") (pintype "passive"))
      (node (ref "R35") (pin "1") (pinfunction "1_1") (pintype "passive"))
    )
    (net (code "70") (name "Net-(Q13-G)") (class "Default")
      (node (ref "Q13") (pin "1") (pinfunction "G_1") (pintype "bidirectional"))
      (node (ref "R37") (pin "1") (pinfunction "1_1") (pintype "passive"))
      (node (ref "R38") (pin "1") (pinfunction "1_1") (pintype "passive"))
    )
    (net (code "71") (name "Net-(Q14-G)") (class "Default")
      (node (ref "Q14") (pin "1") (pinfunction "G_1") (pintype "bidirectional"))
      (node (ref "R40") (pin "1") (pinfunction "1_1") (pintype "passive"))
      (node (ref "R41") (pin "1") (pinfunction "1_1") (pintype "passive"))
    )
    (net (code "72") (name "Net-(Q15-G)") (class "Default")
      (node (ref "Q15") (pin "1") (pinfunction "G_1") (pintype "bidirectional"))
      (node (ref "R43") (pin "1") (pinfunction "1_1") (pintype "passive"))
      (node (ref "R44") (pin "1") (pinfunction "1_1") (pintype "passive"))
    )
    (net (code "73") (name "Net-(Q16-G)") (class "Default")
      (node (ref "Q16") (pin "1") (pinfunction "G_1") (pintype "bidirectional"))
      (node (ref "R46") (pin "1") (pinfunction "1_1") (pintype "passive"))
      (node (ref "R47") (pin "1") (pinfunction "1_1") (pintype "passive"))
    )
    (net (code "74") (name "Net-(Q17-D)") (class "Default")
      (node (ref "Q17") (pin "3") (pinfunction "D_3") (pintype "bidirectional"))
      (node (ref "R9") (pin "2") (pinfunction "2_2") (pintype "passive"))
    )
    (net (code "75") (name "Net-(Q17-G)") (class "Default")
      (node (ref "Q17") (pin "1") (pinfunction "G_1") (pintype "bidirectional"))
      (node (ref "R12") (pin "1") (pinfunction "1_1") (pintype "passive"))
      (node (ref "R15") (pin "1") (pinfunction "1_1") (pintype "passive"))
    )
    (net (code "76") (name "Net-(R2-Pad2)") (class "Default")
      (node (ref "R2") (pin "2") (pinfunction "2_2") (pintype "passive"))
      (node (ref "REV") (pin "C") (pinfunction "C_C") (pintype "passive"))
    )
    (net (code "77") (name "Net-(R82-Pad1)") (class "Default")
      (node (ref "R82") (pin "1") (pinfunction "1_1") (pintype "passive"))
      (node (ref "SECONDS") (pin "A1") (pinfunction "A1_A1") (pintype "bidirectional"))
    )
    (net (code "78") (name "Net-(R83-Pad1)") (class "Default")
      (node (ref "R83") (pin "1") (pinfunction "1_1") (pintype "passive"))
      (node (ref "SECONDS") (pin "B1") (pinfunction "B1_B1") (pintype "bidirectional"))
    )
    (net (code "79") (name "Net-(R84-Pad1)") (class "Default")
      (node (ref "R84") (pin "1") (pinfunction "1_1") (pintype "passive"))
      (node (ref "SECONDS") (pin "C1") (pinfunction "C1_C1") (pintype "bidirectional"))
    )
    (net (code "80") (name "Net-(R85-Pad1)") (class "Default")
      (node (ref "R85") (pin "1") (pinfunction "1_1") (pintype "passive"))
      (node (ref "SECONDS") (pin "D1") (pinfunction "D1_D1") (pintype "bidirectional"))
    )
    (net (code "81") (name "Net-(R86-Pad1)") (class "Default")
      (node (ref "R86") (pin "1") (pinfunction "1_1") (pintype "passive"))
      (node (ref "SECONDS") (pin "E1") (pinfunction "E1_E1") (pintype "bidirectional"))
    )
    (net (code "82") (name "Net-(R87-Pad1)") (class "Default")
      (node (ref "R87") (pin "1") (pinfunction "1_1") (pintype "passive"))
      (node (ref "SECONDS") (pin "F1") (pinfunction "F1_F1") (pintype "bidirectional"))
    )
    (net (code "83") (name "Net-(R88-Pad1)") (class "Default")
      (node (ref "R88") (pin "1") (pinfunction "1_1") (pintype "passive"))
      (node (ref "SECONDS") (pin "G1") (pinfunction "G1_G1") (pintype "bidirectional"))
    )
    (net (code "84") (name "Net-(R89-Pad1)") (class "Default")
      (node (ref "R89") (pin "1") (pinfunction "1_1") (pintype "passive"))
      (node (ref "SECONDS") (pin "DP1") (pinfunction "DP1_DP1") (pintype "bidirectional"))
    )
    (net (code "85") (name "Net-(R90-Pad2)") (class "Default")
      (node (ref "R90") (pin "2") (pinfunction "2_2") (pintype "passive"))
      (node (ref "SECONDS") (pin "A2") (pinfunction "A2_A2") (pintype "bidirectional"))
    )
    (net (code "86") (name "Net-(R91-Pad2)") (class "Default")
      (node (ref "R91") (pin "2") (pinfunction "2_2") (pintype "passive"))
      (node (ref "SECONDS") (pin "B2") (pinfunction "B2_B2") (pintype "bidirectional"))
    )
    (net (code "87") (name "Net-(R92-Pad2)") (class "Default")
      (node (ref "R92") (pin "2") (pinfunction "2_2") (pintype "passive"))
      (node (ref "SECONDS") (pin "C2") (pinfunction "C2_C2") (pintype "bidirectional"))
    )
    (net (code "88") (name "Net-(R93-Pad2)") (class "Default")
      (node (ref "R93") (pin "2") (pinfunction "2_2") (pintype "passive"))
      (node (ref "SECONDS") (pin "D2") (pinfunction "D2_D2") (pintype "bidirectional"))
    )
    (net (code "89") (name "Net-(R94-Pad2)") (class "Default")
      (node (ref "R94") (pin "2") (pinfunction "2_2") (pintype "passive"))
      (node (ref "SECONDS") (pin "E2") (pinfunction "E2_E2") (pintype "bidirectional"))
    )
    (net (code "90") (name "Net-(R95-Pad2)") (class "Default")
      (node (ref "R95") (pin "2") (pinfunction "2_2") (pintype "passive"))
      (node (ref "SECONDS") (pin "F2") (pinfunction "F2_F2") (pintype "bidirectional"))
    )
    (net (code "91") (name "Net-(R96-Pad2)") (class "Default")
      (node (ref "R96") (pin "2") (pinfunction "2_2") (pintype "passive"))
      (node (ref "SECONDS") (pin "G2") (pinfunction "G2_G2") (pintype "bidirectional"))
    )
    (net (code "92") (name "Net-(R97-Pad2)") (class "Default")
      (node (ref "R97") (pin "2") (pinfunction "2_2") (pintype "passive"))
      (node (ref "SECONDS") (pin "DP2") (pinfunction "DP2_DP2") (pintype "bidirectional"))
    )
    (net (code "93") (name "Net-(R98-Pad1)") (class "Default")
      (node (ref "R98") (pin "1") (pinfunction "1_1") (pintype "passive"))
      (node (ref "TENS_SEC") (pin "A") (pinfunction "A_A") (pintype "bidirectional"))
    )
    (net (code "94") (name "Net-(R99-Pad1)") (class "Default")
      (node (ref "R99") (pin "1") (pinfunction "1_1") (pintype "passive"))
      (node (ref "TENS_SEC") (pin "B") (pinfunction "B_B") (pintype "bidirectional"))
    )
    (net (code "95") (name "Net-(R100-Pad1)") (class "Default")
      (node (ref "R100") (pin "1") (pinfunction "1_1") (pintype "passive"))
      (node (ref "TENS_SEC") (pin "C") (pinfunction "C_C") (pintype "bidirectional"))
    )
    (net (code "96") (name "Net-(R101-Pad1)") (class "Default")
      (node (ref "R101") (pin "1") (pinfunction "1_1") (pintype "passive"))
      (node (ref "TENS_SEC") (pin "D") (pinfunction "D_D") (pintype "bidirectional"))
    )
    (net (code "97") (name "Net-(R102-Pad1)") (class "Default")
      (node (ref "R102") (pin "1") (pinfunction "1_1") (pintype "passive"))
      (node (ref "TENS_SEC") (pin "E") (pinfunction "E_E") (pintype "bidirectional"))
    )
    (net (code "98") (name "Net-(R103-Pad1)") (class "Default")
      (node (ref "R103") (pin "1") (pinfunction "1_1") (pintype "passive"))
      (node (ref "TENS_SEC") (pin "F") (pinfunction "F_F") (pintype "bidirectional"))
    )
    (net (code "99") (name "Net-(R104-Pad1)") (class "Default")
      (node (ref "R104") (pin "1") (pinfunction "1_1") (pintype "passive"))
      (node (ref "TENS_SEC") (pin "G") (pinfunction "G_G") (pintype "bidirectional"))
    )
    (net (code "100") (name "Net-(R105-Pad1)") (class "Default")
      (node (ref "R105") (pin "1") (pinfunction "1_1") (pintype "passive"))
      (node (ref "TENS_SEC") (pin "DP") (pinfunction "DP_DP") (pintype "bidirectional"))
    )
    (net (code "101") (name "Net-(U1-PB0(ICP))") (class "Default")
      (node (ref "CLOCK") (pin "1") (pinfunction "1_1") (pintype "passive"))
      (node (ref "U1") (pin "12") (pinfunction "PB0(ICP)_12") (pintype "bidirectional"))
    )
    (net (code "102") (name "Net-(U1-PB6(XTAL1{slash}TOSC1))") (class "Default")
      (node (ref "C4") (pin "2") (pinfunction "2_2") (pintype "passive"))
      (node (ref "U1") (pin "7") (pinfunction "PB6(XTAL1/TOSC1)_7") (pintype "bidirectional"))
      (node (ref "X1") (pin "2") (pinfunction "2_2") (pintype "passive"))
    )
    (net (code "103") (name "Net-(U1-PB7(XTAL2{slash}TOSC2))") (class "Default")
      (node (ref "C3") (pin "2") (pinfunction "2_2") (pintype "passive"))
      (node (ref "U1") (pin "8") (pinfunction "PB7(XTAL2/TOSC2)_8") (pintype "bidirectional"))
      (node (ref "X1") (pin "1") (pinfunction "1_1") (pintype "passive"))
    )
    (net (code "104") (name "Net-(U1-PD2(INT0))") (class "Default")
      (node (ref "ALARM_SET") (pin "1") (pinfunction "1_1") (pintype "passive"))
      (node (ref "U1") (pin "32") (pinfunction "PD2(INT0)_32") (pintype "bidirectional"))
    )
    (net (code "105") (name "Net-(U1-PD5(T1))") (class "Default")
      (node (ref "ALARM_ARM") (pin "1") (pinfunction "1_1") (pintype "passive"))
      (node (ref "U1") (pin "9") (pinfunction "PD5(T1)_9") (pintype "bidirectional"))
    )
    (net (code "106") (name "Net-(U1-PD6(AIN0))") (class "Default")
      (node (ref "DATE") (pin "1") (pinfunction "1_1") (pintype "passive"))
      (node (ref "U1") (pin "10") (pinfunction "PD6(AIN0)_10") (pintype "bidirectional"))
    )
    (net (code "107") (name "Net-(U1-PD7(AIN1))") (class "Default")
      (node (ref "TEMP") (pin "1") (pinfunction "1_1") (pintype "passive"))
      (node (ref "U1") (pin "11") (pinfunction "PD7(AIN1)_11") (pintype "bidirectional"))
    )
    (net (code "108") (name "Q0.1") (class "Default")
      (node (ref "7_SEGMENT") (pin "15") (pinfunction "Q0_15") (pintype "tri_state"))
      (node (ref "R4") (pin "2") (pinfunction "2_2") (pintype "passive"))
    )
    (net (code "109") (name "Q0.2") (class "Default")
      (node (ref "DIGIT_POS") (pin "15") (pinfunction "Q0_15") (pintype "tri_state"))
      (node (ref "R46") (pin "2") (pinfunction "2_2") (pintype "passive"))
    )
    (net (code "110") (name "Q1.1") (class "Default")
      (node (ref "7_SEGMENT") (pin "1") (pinfunction "Q1_1") (pintype "tri_state"))
      (node (ref "R7") (pin "2") (pinfunction "2_2") (pintype "passive"))
    )
    (net (code "111") (name "Q1.2") (class "Default")
      (node (ref "DIGIT_POS") (pin "1") (pinfunction "Q1_1") (pintype "tri_state"))
      (node (ref "R43") (pin "2") (pinfunction "2_2") (pintype "passive"))
    )
    (net (code "112") (name "Q2.1") (class "Default")
      (node (ref "7_SEGMENT") (pin "2") (pinfunction "Q2_2") (pintype "tri_state"))
      (node (ref "R10") (pin "2") (pinfunction "2_2") (pintype "passive"))
    )
    (net (code "113") (name "Q2.2") (class "Default")
      (node (ref "DIGIT_POS") (pin "2") (pinfunction "Q2_2") (pintype "tri_state"))
      (node (ref "R40") (pin "2") (pinfunction "2_2") (pintype "passive"))
    )
    (net (code "114") (name "Q3.1") (class "Default")
      (node (ref "7_SEGMENT") (pin "3") (pinfunction "Q3_3") (pintype "tri_state"))
      (node (ref "R13") (pin "2") (pinfunction "2_2") (pintype "passive"))
    )
    (net (code "115") (name "Q3.2") (class "Default")
      (node (ref "DIGIT_POS") (pin "3") (pinfunction "Q3_3") (pintype "tri_state"))
      (node (ref "R37") (pin "2") (pinfunction "2_2") (pintype "passive"))
    )
    (net (code "116") (name "Q4.1") (class "Default")
      (node (ref "7_SEGMENT") (pin "4") (pinfunction "Q4_4") (pintype "tri_state"))
      (node (ref "R16") (pin "2") (pinfunction "2_2") (pintype "passive"))
    )
    (net (code "117") (name "Q4.2") (class "Default")
      (node (ref "DIGIT_POS") (pin "4") (pinfunction "Q4_4") (pintype "tri_state"))
      (node (ref "R34") (pin "2") (pinfunction "2_2") (pintype "passive"))
    )
    (net (code "118") (name "Q5.1") (class "Default")
      (node (ref "7_SEGMENT") (pin "5") (pinfunction "Q5_5") (pintype "tri_state"))
      (node (ref "R19") (pin "2") (pinfunction "2_2") (pintype "passive"))
    )
    (net (code "119") (name "Q5.2") (class "Default")
      (node (ref "DIGIT_POS") (pin "5") (pinfunction "Q5_5") (pintype "tri_state"))
      (node (ref "R31") (pin "2") (pinfunction "2_2") (pintype "passive"))
    )
    (net (code "120") (name "Q6.1") (class "Default")
      (node (ref "7_SEGMENT") (pin "6") (pinfunction "Q6_6") (pintype "tri_state"))
      (node (ref "R22") (pin "2") (pinfunction "2_2") (pintype "passive"))
    )
    (net (code "121") (name "Q6.2") (class "Default")
      (node (ref "DIGIT_POS") (pin "6") (pinfunction "Q6_6") (pintype "tri_state"))
      (node (ref "R28") (pin "2") (pinfunction "2_2") (pintype "passive"))
    )
    (net (code "122") (name "Q7.1") (class "Default")
      (node (ref "7_SEGMENT") (pin "7") (pinfunction "Q7_7") (pintype "tri_state"))
      (node (ref "R25") (pin "2") (pinfunction "2_2") (pintype "passive"))
    )
    (net (code "123") (name "RESET") (class "Default")
      (node (ref "ICSP") (pin "2") (pinfunction "2_2") (pintype "passive"))
      (node (ref "U1") (pin "29") (pinfunction "PC6(/RESET)_29") (pintype "bidirectional"))
    )
    (net (code "124") (name "RX") (class "Default")
      (node (ref "U1") (pin "30") (pinfunction "PD0(RXD)_30") (pintype "bidirectional"))
      (node (ref "UART") (pin "2") (pinfunction "2_2") (pintype "passive"))
    )
    (net (code "125") (name "SCK") (class "Default")
      (node (ref "ICSP") (pin "4") (pinfunction "4_4") (pintype "passive"))
      (node (ref "U1") (pin "17") (pinfunction "PB5(SCK)_17") (pintype "bidirectional"))
    )
    (net (code "126") (name "SCL") (class "Default")
      (node (ref "DS3231") (pin "4") (pinfunction "4_4") (pintype "passive"))
      (node (ref "LCD") (pin "3") (pinfunction "3_3") (pintype "passive"))
      (node (ref "R6") (pin "2") (pinfunction "2_2") (pintype "passive"))
      (node (ref "U1") (pin "28") (pinfunction "PC5(ADC5/SCL)_28") (pintype "bidirectional"))
    )
    (net (code "127") (name "SDA") (class "Default")
      (node (ref "DS3231") (pin "3") (pinfunction "3_3") (pintype "passive"))
      (node (ref "LCD") (pin "4") (pinfunction "4_4") (pintype "passive"))
      (node (ref "R3") (pin "2") (pinfunction "2_2") (pintype "passive"))
      (node (ref "U1") (pin "27") (pinfunction "PC4(ADC4/SDA)_27") (pintype "bidirectional"))
    )
    (net (code "128") (name "SEC_1") (class "Default")
      (node (ref "Q14") (pin "3") (pinfunction "D_3") (pintype "bidirectional"))
      (node (ref "SECONDS") (pin "GND1") (pinfunction "GND1_GND1") (pintype "bidirectional"))
    )
    (net (code "129") (name "SEC_2") (class "Default")
      (node (ref "Q15") (pin "3") (pinfunction "D_3") (pintype "bidirectional"))
      (node (ref "SECONDS") (pin "GND2") (pinfunction "GND2_GND2") (pintype "bidirectional"))
    )
    (net (code "130") (name "SHCP") (class "Default")
      (node (ref "7_SEGMENT") (pin "11") (pinfunction "SHCP_11") (pintype "input"))
      (node (ref "DIGIT_POS") (pin "11") (pinfunction "SHCP_11") (pintype "input"))
      (node (ref "U1") (pin "24") (pinfunction "PC1(ADC1)_24") (pintype "bidirectional"))
    )
    (net (code "131") (name "STCP") (class "Default")
      (node (ref "7_SEGMENT") (pin "12") (pinfunction "STCP_12") (pintype "input"))
      (node (ref "DIGIT_POS") (pin "12") (pinfunction "STCP_12") (pintype "input"))
      (node (ref "U1") (pin "25") (pinfunction "PC2(ADC2)_25") (pintype "bidirectional"))
    )
    (net (code "132") (name "TENS") (class "Default")
      (node (ref "Q16") (pin "3") (pinfunction "D_3") (pintype "bidirectional"))
      (node (ref "TENS_SEC") (pin "GND") (pinfunction "GND_GND") (pintype "bidirectional"))
      (node (ref "TENS_SEC") (pin "GND1") (pinfunction "GND1_GND1") (pintype "bidirectional"))
    )
    (net (code "133") (name "TX") (class "Default")
      (node (ref "U1") (pin "31") (pinfunction "PD1(TXD)_31") (pintype "bidirectional"))
      (node (ref "UART") (pin "1") (pinfunction "1_1") (pintype "passive"))
    )
    (net (code "134") (name "VCC") (class "Default")
      (node (ref "BYPASS_REG") (pin "2") (pinfunction "2_2") (pintype "passive"))
      (node (ref "C1") (pin "1") (pinfunction "1_1") (pintype "passive"))
      (node (ref "IC2") (pin "1") (pinfunction "VI_1") (pintype "input"))
      (node (ref "J1") (pin "1") (pinfunction "1_1") (pintype "passive"))
      (node (ref "R1") (pin "1") (pinfunction "1_1") (pintype "passive"))
      (node (ref "R2") (pin "1") (pinfunction "1_1") (pintype "passive"))
    )
    (net (code "135") (name "VCC_1") (class "Default")
      (node (ref "BYPASS_REG") (pin "1") (pinfunction "1_1") (pintype "passive"))
      (node (ref "C2") (pin "1") (pinfunction "1_1") (pintype "passive"))
      (node (ref "IC2") (pin "2") (pinfunction "VO_2") (pintype "passive"))
      (node (ref "ON") (pin "1") (pinfunction "O_1") (pintype "passive"))
      (node (ref "ON") (pin "2") (pinfunction "P_2") (pintype "passive"))
      (node (ref "USB") (pin "1") (pinfunction "VBUS_1") (pintype "passive"))
    )
    (net (code "136") (name "unconnected-(DIGIT_POS-Q7*-Pad9)") (class "Default")
      (node (ref "DIGIT_POS") (pin "9") (pinfunction "Q7*_9") (pintype "tri_state"))
    )
    (net (code "137") (name "unconnected-(DIGIT_POS-Q7-Pad7)") (class "Default")
      (node (ref "DIGIT_POS") (pin "7") (pinfunction "Q7_7") (pintype "tri_state"))
    )
    (net (code "138") (name "unconnected-(U1-ADC6-Pad19)") (class "Default")
      (node (ref "U1") (pin "19") (pinfunction "ADC6_19") (pintype "bidirectional"))
    )
    (net (code "139") (name "unconnected-(U1-ADC7-Pad22)") (class "Default")
      (node (ref "U1") (pin "22") (pinfunction "ADC7_22") (pintype "bidirectional"))
    )
    (net (code "140") (name "unconnected-(U1-PB1(OC1A)-Pad13)") (class "Default")
      (node (ref "U1") (pin "13") (pinfunction "PB1(OC1A)_13") (pintype "bidirectional"))
    )
    (net (code "141") (name "unconnected-(U1-PB2(SS{slash}OC1B)-Pad14)") (class "Default")
      (node (ref "U1") (pin "14") (pinfunction "PB2(SS/OC1B)_14") (pintype "bidirectional"))
    )
    (net (code "142") (name "unconnected-(U1-PC3(ADC3)-Pad26)") (class "Default")
      (node (ref "U1") (pin "26") (pinfunction "PC3(ADC3)_26") (pintype "bidirectional"))
    )
    (net (code "143") (name "unconnected-(U1-PD4(XCK{slash}T0)-Pad2)") (class "Default")
      (node (ref "U1") (pin "2") (pinfunction "PD4(XCK/T0)_2") (pintype "bidirectional"))
    )
    (net (code "144") (name "unconnected-(USB-D+-Pad3)") (class "Default")
      (node (ref "USB") (pin "3") (pinfunction "D+_3") (pintype "passive"))
    )
    (net (code "145") (name "unconnected-(USB-D--Pad2)") (class "Default")
      (node (ref "USB") (pin "2") (pinfunction "D-_2") (pintype "passive"))
    )
    (net (code "146") (name "unconnected-(USB-ID-Pad4)") (class "Default")
      (node (ref "USB") (pin "4") (pinfunction "ID_4") (pintype "passive"))
    )
  )
)
